# LaserDiode.net
KiCad netlist of a schematic drawn in Altium Designer
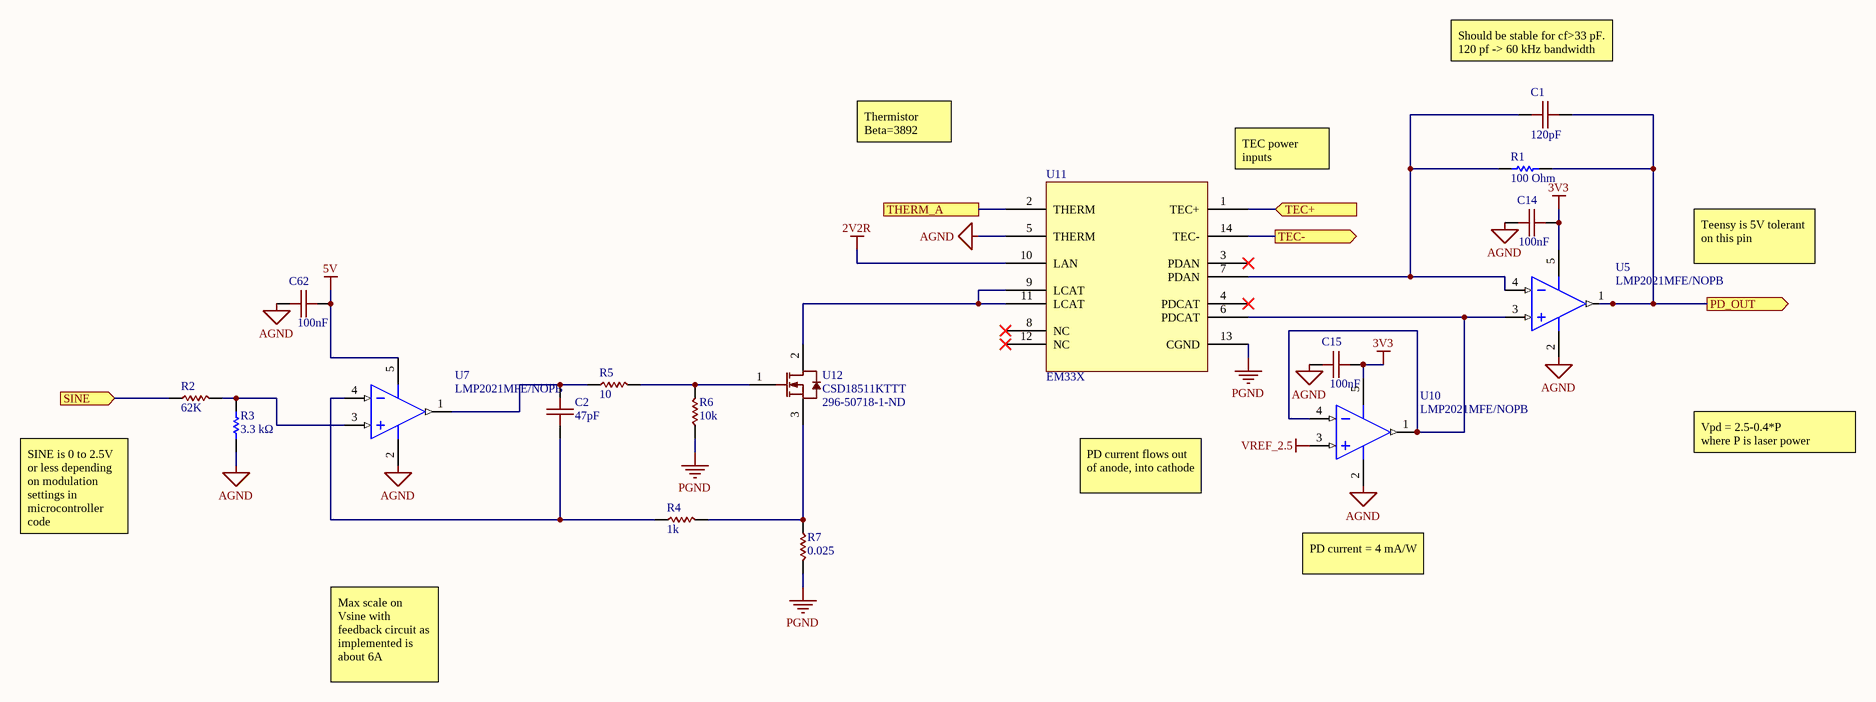
[diagram p0: LaserDiode.SchDoc]

(export (version "E")
  (design (tool "Eeschema 10.0.6"))
  (components
    (comp (ref "C1")
      (value "120pF")
      (footprint "0603 B")
      (description "Cap Ceramic 120pF 50V C0G 5% SMD 0603 125°C Paper T/R")
      (fields
        (field (name "MANUFACTURER") "KEMET")
        (field (name "MANUFACTURER PART NUMBER") "C0603C121J5GACTU")
      )
      (libsource (lib "PSSL3") (part "CAP 0603"))
    )
    (comp (ref "C2")
      (value "47pF")
      (footprint "0603 B")
      (description "603 Capacitor")
      (libsource (lib "PSSL3") (part "CAP 0603"))
    )
    (comp (ref "C14")
      (value "100nF")
      (footprint "0603 B")
      (description "603 Capacitor")
      (libsource (lib "PSSL3") (part "CAP 0603"))
    )
    (comp (ref "C15")
      (value "100nF")
      (footprint "0603 B")
      (description "603 Capacitor")
      (libsource (lib "PSSL3") (part "CAP 0603"))
    )
    (comp (ref "C62")
      (value "100nF")
      (footprint "0603 B")
      (description "603 Capacitor")
      (libsource (lib "PSSL3") (part "CAP 0603"))
    )
    (comp (ref "R1")
      (value "100 Ohm")
      (footprint "RESC1608X55X30LL15T15")
      (fields (field (name "MANUFACTURER") "Panasonic") (field (name "PART NUMBER") "ERJ-3EKF1000V"))
      (libsource (lib "Altium Content Vault") (part "RES"))
    )
    (comp (ref "R2")
      (value "62K")
      (footprint "0805")
      (description "805 Resistor")
      (libsource (lib "PSSL3") (part "RES 0805"))
    )
    (comp (ref "R3")
      (value "3.3 kΩ")
      (footprint "RESC2013X70X40ML20T20")
      (fields (field (name "MANUFACTURER") "Panasonic") (field (name "PART NUMBER") "ERJ6ENF3301V"))
      (libsource (lib "Altium Content Vault") (part "RES"))
    )
    (comp (ref "R4")
      (value "1k")
      (footprint "0805")
      (description "805 Resistor")
      (libsource (lib "PSSL3") (part "RES 0805"))
    )
    (comp (ref "R5")
      (value "10")
      (footprint "0805")
      (description "805 Resistor")
      (libsource (lib "PSSL3") (part "RES 0805"))
    )
    (comp (ref "R6")
      (value "10k")
      (footprint "0805")
      (description "805 Resistor")
      (libsource (lib "PSSL3") (part "RES 0805"))
    )
    (comp (ref "R7")
      (value "0.025")
      (footprint "1206")
      (description "1206 Resistor")
      (libsource (lib "PSSL3") (part "RES 1206"))
    )
    (comp (ref "U5")
      (value "LMP2021MFE/NOPB")
      (footprint "DBV0005A_N")
      (description "Zero Drift, Low Noise, EMI Hardened Amplifier, 5-pin SOT-23, Pb-Free")
      (fields (field (name "MANUFACTURER") "Texas Instruments"))
      (libsource (lib "Altium Content Vault") (part "AMP-OPA-LM7121-5"))
    )
    (comp (ref "U7")
      (value "LMP2021MFE/NOPB")
      (footprint "DBV0005A_N")
      (description "Zero Drift, Low Noise, EMI Hardened Amplifier, 5-pin SOT-23, Pb-Free")
      (fields (field (name "MANUFACTURER") "Texas Instruments"))
      (libsource (lib "Altium Content Vault") (part "AMP-OPA-LM7121-5"))
    )
    (comp (ref "U10")
      (value "LMP2021MFE/NOPB")
      (footprint "DBV0005A_N")
      (description "Zero Drift, Low Noise, EMI Hardened Amplifier, 5-pin SOT-23, Pb-Free")
      (fields (field (name "MANUFACTURER") "Texas Instruments"))
      (libsource (lib "Altium Content Vault") (part "AMP-OPA-LM7121-5"))
    )
    (comp (ref "U11")
      (value "EM33X")
      (footprint "EM33X")
      (description "5W Cooled 9XX Multimode Lasers in 14-Pin Package")
      (libsource (lib "BeaconBoard") (part "EM33X"))
    )
    (comp (ref "U12")
      (value "CSD18511KTTT")
      (footprint "DPAK254P1510X470-3N")
      (description "40-V, N channel NexFET™ power MOSFET, single D2PAK, 2.6 mOhm")
      (fields
        (field (name "MANUFACTURER_PART_NUMBER") "CSD18511KTT")
        (field (name "SUPPLIER PART NUMBER 1") "296-50718-1-ND")
        (field (name "COPYRIGHT") "Copyright (C) 2018 Accelerated Designs. All rights reserved")
      )
      (libsource (lib "BeaconBoard") (part "CSD18511KTT"))
    )
  )
  (nets
    (net (code "1") (name "/PD_OUT") (class "Default")
      (node (ref "C1") (pin "1") (pintype "passive"))
      (node (ref "R1") (pin "2") (pinfunction "2_2") (pintype "passive"))
      (node (ref "U5") (pin "1") (pinfunction "OUT_1") (pintype "output"))
    )
    (net (code "2") (name "/SINE") (class "Default") (node (ref "R2") (pin "2") (pintype "passive")))
    (net (code "3") (name "/TEC+") (class "Default")
      (node (ref "U11") (pin "1") (pinfunction "TEC+_1") (pintype "passive"))
    )
    (net (code "4") (name "/TEC-") (class "Default")
      (node (ref "U11") (pin "14") (pinfunction "TEC-_14") (pintype "passive"))
    )
    (net (code "5") (name "/THERM_A") (class "Default")
      (node (ref "U11") (pin "2") (pinfunction "THERM_2") (pintype "passive"))
    )
    (net (code "6") (name "2V2R") (class "Default")
      (node (ref "U11") (pin "10") (pinfunction "LAN_10") (pintype "passive"))
    )
    (net (code "7") (name "3V3") (class "Default")
      (node (ref "C14") (pin "1") (pintype "passive"))
      (node (ref "C15") (pin "1") (pintype "passive"))
      (node (ref "U10") (pin "5") (pinfunction "V+_5") (pintype "power_in"))
      (node (ref "U5") (pin "5") (pinfunction "V+_5") (pintype "power_in"))
    )
    (net (code "8") (name "5V") (class "Default")
      (node (ref "C62") (pin "1") (pintype "passive"))
      (node (ref "U7") (pin "5") (pinfunction "V+_5") (pintype "power_in"))
    )
    (net (code "9") (name "AGND") (class "Default")
      (node (ref "C14") (pin "2") (pintype "passive"))
      (node (ref "C15") (pin "2") (pintype "passive"))
      (node (ref "C62") (pin "2") (pintype "passive"))
      (node (ref "R3") (pin "1") (pinfunction "1_1") (pintype "passive"))
      (node (ref "U10") (pin "2") (pinfunction "V-_2") (pintype "power_in"))
      (node (ref "U11") (pin "5") (pinfunction "THERM_5") (pintype "passive"))
      (node (ref "U5") (pin "2") (pinfunction "V-_2") (pintype "power_in"))
      (node (ref "U7") (pin "2") (pinfunction "V-_2") (pintype "power_in"))
    )
    (net (code "10") (name "Net-(U5-IN-)") (class "Default")
      (node (ref "C1") (pin "2") (pintype "passive"))
      (node (ref "R1") (pin "1") (pinfunction "1_1") (pintype "passive"))
      (node (ref "U11") (pin "7") (pinfunction "PDAN_7") (pintype "passive"))
      (node (ref "U5") (pin "4") (pinfunction "IN-_4") (pintype "input"))
    )
    (net (code "11") (name "Net-(U7-IN+)") (class "Default")
      (node (ref "R2") (pin "1") (pintype "passive"))
      (node (ref "R3") (pin "2") (pinfunction "2_2") (pintype "passive"))
      (node (ref "U7") (pin "3") (pinfunction "IN+_3") (pintype "input"))
    )
    (net (code "12") (name "Net-(U7-IN-)") (class "Default")
      (node (ref "C2") (pin "1") (pintype "passive"))
      (node (ref "R4") (pin "2") (pintype "passive"))
      (node (ref "U7") (pin "4") (pinfunction "IN-_4") (pintype "input"))
    )
    (net (code "13") (name "Net-(U7-OUT)") (class "Default")
      (node (ref "C2") (pin "2") (pintype "passive"))
      (node (ref "R5") (pin "2") (pintype "passive"))
      (node (ref "U7") (pin "1") (pinfunction "OUT_1") (pintype "output"))
    )
    (net (code "14") (name "Net-(U10-IN-)") (class "Default")
      (node (ref "U10") (pin "1") (pinfunction "OUT_1") (pintype "output"))
      (node (ref "U10") (pin "4") (pinfunction "IN-_4") (pintype "input"))
      (node (ref "U11") (pin "6") (pinfunction "PDCAT_6") (pintype "passive"))
      (node (ref "U5") (pin "3") (pinfunction "IN+_3") (pintype "input"))
    )
    (net (code "15") (name "Net-(U12-D)") (class "Default")
      (node (ref "U11") (pin "11") (pinfunction "LCAT_11") (pintype "passive"))
      (node (ref "U11") (pin "9") (pinfunction "LCAT_9") (pintype "passive"))
      (node (ref "U12") (pin "2") (pinfunction "D_2") (pintype "passive"))
    )
    (net (code "16") (name "Net-(U12-G)") (class "Default")
      (node (ref "R5") (pin "1") (pintype "passive"))
      (node (ref "R6") (pin "1") (pintype "passive"))
      (node (ref "U12") (pin "1") (pinfunction "G_1") (pintype "passive"))
    )
    (net (code "17") (name "Net-(U12-S)") (class "Default")
      (node (ref "R4") (pin "1") (pintype "passive"))
      (node (ref "R7") (pin "2") (pintype "passive"))
      (node (ref "U12") (pin "3") (pinfunction "S_3") (pintype "passive"))
    )
    (net (code "18") (name "PGND") (class "Default")
      (node (ref "R6") (pin "2") (pintype "passive"))
      (node (ref "R7") (pin "1") (pintype "passive"))
      (node (ref "U11") (pin "13") (pinfunction "CGND_13") (pintype "passive"))
    )
    (net (code "19") (name "VREF_2.5") (class "Default")
      (node (ref "U10") (pin "3") (pinfunction "IN+_3") (pintype "input"))
    )
    (net (code "20") (name "unconnected-(U11-NC-Pad8)") (class "Default")
      (node (ref "U11") (pin "8") (pinfunction "NC_8") (pintype "passive+no_connect"))
    )
    (net (code "21") (name "unconnected-(U11-NC-Pad12)") (class "Default")
      (node (ref "U11") (pin "12") (pinfunction "NC_12") (pintype "passive+no_connect"))
    )
    (net (code "22") (name "unconnected-(U11-PDAN-Pad3)") (class "Default")
      (node (ref "U11") (pin "3") (pinfunction "PDAN_3") (pintype "passive+no_connect"))
    )
    (net (code "23") (name "unconnected-(U11-PDCAT-Pad4)") (class "Default")
      (node (ref "U11") (pin "4") (pinfunction "PDCAT_4") (pintype "passive+no_connect"))
    )
  )
)
